# ftdi.net
KiCad netlist of a schematic drawn in Altium Designer
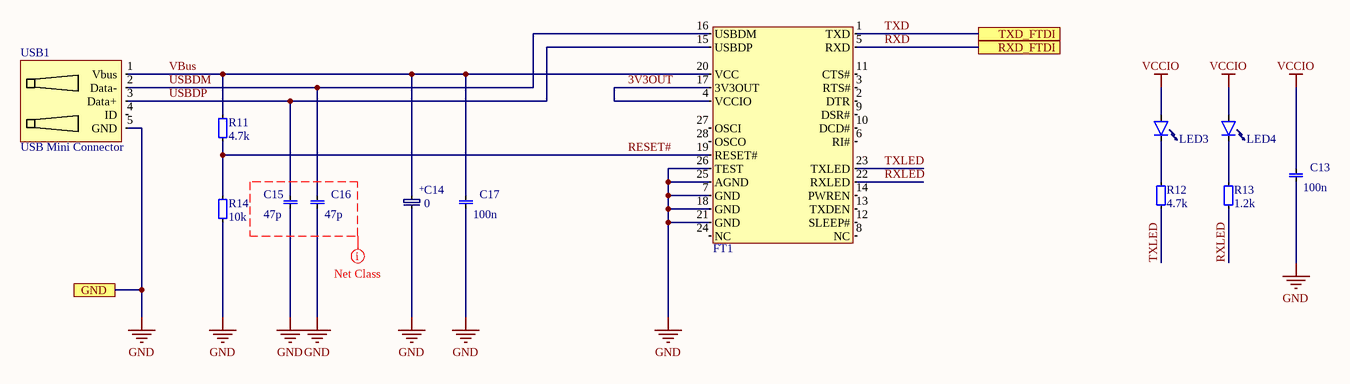
[diagram p0: ftdi.SchDoc]

(export (version "E")
  (design (tool "Eeschema 10.0.6"))
  (components
    (comp (ref "C13")
      (value "100n")
      (footprint "0603 cap")
      (fields (field (name "Comment") "0603, capacitor"))
      (libsource (lib "jclib") (part "0603, capacitor"))
    )
    (comp (ref "C14")
      (value "0")
      (footprint "CASE_B")
      (fields (field (name "Comment") "Cap, case B"))
      (libsource (lib "jclib") (part "Cap, case B"))
    )
    (comp (ref "C15")
      (value "47p")
      (footprint "0603 cap")
      (fields (field (name "Comment") "0603, capacitor"))
      (libsource (lib "jclib") (part "0603, capacitor"))
    )
    (comp (ref "C16")
      (value "47p")
      (footprint "0603 cap")
      (fields (field (name "Comment") "0603, capacitor"))
      (libsource (lib "jclib") (part "0603, capacitor"))
    )
    (comp (ref "C17")
      (value "100n")
      (footprint "0603 cap")
      (fields (field (name "Comment") "0603, capacitor"))
      (libsource (lib "jclib") (part "0603, capacitor"))
    )
    (comp (ref "FT1")
      (value "FT232R")
      (footprint "SOP28")
      (description "USB UART IC")
      (libsource (lib "jclib") (part "FT232R"))
    )
    (comp (ref "LED3")
      (value "0805, LED")
      (footprint "0805_led")
      (libsource (lib "jclib") (part "0805, LED"))
    )
    (comp (ref "LED4")
      (value "0805, LED")
      (footprint "0805_led")
      (libsource (lib "jclib") (part "0805, LED"))
    )
    (comp (ref "R11")
      (value "4.7k")
      (footprint "0603")
      (fields (field (name "Comment") "0603, resistor"))
      (libsource (lib "jclib") (part "0603, resistor"))
    )
    (comp (ref "R12")
      (value "4.7k")
      (footprint "0603")
      (fields (field (name "Comment") "0603, resistor"))
      (libsource (lib "jclib") (part "0603, resistor"))
    )
    (comp (ref "R13")
      (value "1.2k")
      (footprint "0603")
      (fields (field (name "Comment") "0603, resistor"))
      (libsource (lib "jclib") (part "0603, resistor"))
    )
    (comp (ref "R14")
      (value "10k")
      (footprint "0603")
      (fields (field (name "Comment") "0603, resistor"))
      (libsource (lib "jclib") (part "0603, resistor"))
    )
    (comp (ref "USB1")
      (value "USB Mini Connector")
      (footprint "USB Mini TH")
      (libsource (lib "jclib") (part "USB Mini Connector"))
    )
  )
  (nets
    (net (code "1") (name "/3V3OUT") (class "Default")
      (node (ref "FT1") (pin "17") (pinfunction "3V3OUT_17") (pintype "passive"))
      (node (ref "FT1") (pin "4") (pinfunction "VCCIO_4") (pintype "passive"))
    )
    (net (code "2") (name "/RESET#") (class "Default")
      (node (ref "FT1") (pin "19") (pinfunction "RESET#_19") (pintype "passive"))
      (node (ref "R11") (pin "1") (pinfunction "1_1") (pintype "passive"))
      (node (ref "R14") (pin "0") (pinfunction "0_0") (pintype "passive"))
    )
    (net (code "3") (name "/RXD") (class "Default")
      (node (ref "FT1") (pin "5") (pinfunction "RXD_5") (pintype "passive"))
    )
    (net (code "4") (name "/RXLED") (class "Default")
      (node (ref "FT1") (pin "22") (pinfunction "RXLED_22") (pintype "passive"))
      (node (ref "R13") (pin "1") (pinfunction "1_1") (pintype "passive"))
    )
    (net (code "5") (name "/TXD") (class "Default")
      (node (ref "FT1") (pin "1") (pinfunction "TXD_1") (pintype "passive"))
    )
    (net (code "6") (name "/TXLED") (class "Default")
      (node (ref "FT1") (pin "23") (pinfunction "TXLED_23") (pintype "passive"))
      (node (ref "R12") (pin "1") (pinfunction "1_1") (pintype "passive"))
    )
    (net (code "7") (name "/USBDM") (class "Default")
      (node (ref "C16") (pin "1") (pinfunction "1_1") (pintype "passive"))
      (node (ref "FT1") (pin "16") (pinfunction "USBDM_16") (pintype "passive"))
      (node (ref "USB1") (pin "2") (pinfunction "Data-_2") (pintype "passive"))
    )
    (net (code "8") (name "/USBDP") (class "Default")
      (node (ref "C15") (pin "1") (pinfunction "1_1") (pintype "passive"))
      (node (ref "FT1") (pin "15") (pinfunction "USBDP_15") (pintype "passive"))
      (node (ref "USB1") (pin "3") (pinfunction "Data+_3") (pintype "passive"))
    )
    (net (code "9") (name "/VBus") (class "Default")
      (node (ref "C14") (pin "2") (pinfunction "2_2") (pintype "passive"))
      (node (ref "C17") (pin "1") (pinfunction "1_1") (pintype "passive"))
      (node (ref "FT1") (pin "20") (pinfunction "VCC_20") (pintype "passive"))
      (node (ref "R11") (pin "0") (pinfunction "0_0") (pintype "passive"))
      (node (ref "USB1") (pin "1") (pinfunction "Vbus_1") (pintype "passive"))
    )
    (net (code "10") (name "GND") (class "Default")
      (node (ref "C13") (pin "0") (pinfunction "0_0") (pintype "passive"))
      (node (ref "C14") (pin "1") (pinfunction "1_1") (pintype "passive"))
      (node (ref "C15") (pin "0") (pinfunction "0_0") (pintype "passive"))
      (node (ref "C16") (pin "0") (pinfunction "0_0") (pintype "passive"))
      (node (ref "C17") (pin "0") (pinfunction "0_0") (pintype "passive"))
      (node (ref "FT1") (pin "18") (pinfunction "GND_18") (pintype "passive"))
      (node (ref "FT1") (pin "21") (pinfunction "GND_21") (pintype "passive"))
      (node (ref "FT1") (pin "25") (pinfunction "AGND_25") (pintype "passive"))
      (node (ref "FT1") (pin "26") (pinfunction "TEST_26") (pintype "passive"))
      (node (ref "FT1") (pin "7") (pinfunction "GND_7") (pintype "passive"))
      (node (ref "R14") (pin "1") (pinfunction "1_1") (pintype "passive"))
      (node (ref "USB1") (pin "5") (pinfunction "GND_5") (pintype "passive"))
    )
    (net (code "11") (name "Net-(LED3-Cathode)") (class "Default")
      (node (ref "LED3") (pin "0") (pinfunction "Cathode_0") (pintype "passive"))
      (node (ref "R12") (pin "0") (pinfunction "0_0") (pintype "passive"))
    )
    (net (code "12") (name "Net-(LED4-Cathode)") (class "Default")
      (node (ref "LED4") (pin "0") (pinfunction "Cathode_0") (pintype "passive"))
      (node (ref "R13") (pin "0") (pinfunction "0_0") (pintype "passive"))
    )
    (net (code "13") (name "VCCIO") (class "Default")
      (node (ref "C13") (pin "1") (pinfunction "1_1") (pintype "passive"))
      (node (ref "LED3") (pin "1") (pinfunction "1_1") (pintype "passive"))
      (node (ref "LED4") (pin "1") (pinfunction "1_1") (pintype "passive"))
    )
    (net (code "14") (name "unconnected-(FT1-CTS#-Pad11)") (class "Default")
      (node (ref "FT1") (pin "11") (pinfunction "CTS#_11") (pintype "passive"))
    )
    (net (code "15") (name "unconnected-(FT1-DCD#-Pad10)") (class "Default")
      (node (ref "FT1") (pin "10") (pinfunction "DCD#_10") (pintype "passive"))
    )
    (net (code "16") (name "unconnected-(FT1-DSR#-Pad9)") (class "Default")
      (node (ref "FT1") (pin "9") (pinfunction "DSR#_9") (pintype "passive"))
    )
    (net (code "17") (name "unconnected-(FT1-DTR-Pad2)") (class "Default")
      (node (ref "FT1") (pin "2") (pinfunction "DTR_2") (pintype "passive"))
    )
    (net (code "18") (name "unconnected-(FT1-NC-Pad8)") (class "Default")
      (node (ref "FT1") (pin "8") (pinfunction "NC_8") (pintype "passive"))
    )
    (net (code "19") (name "unconnected-(FT1-NC-Pad24)") (class "Default")
      (node (ref "FT1") (pin "24") (pinfunction "NC_24") (pintype "passive"))
    )
    (net (code "20") (name "unconnected-(FT1-OSCI-Pad27)") (class "Default")
      (node (ref "FT1") (pin "27") (pinfunction "OSCI_27") (pintype "passive"))
    )
    (net (code "21") (name "unconnected-(FT1-OSCO-Pad28)") (class "Default")
      (node (ref "FT1") (pin "28") (pinfunction "OSCO_28") (pintype "passive"))
    )
    (net (code "22") (name "unconnected-(FT1-PWREN-Pad14)") (class "Default")
      (node (ref "FT1") (pin "14") (pinfunction "PWREN_14") (pintype "passive"))
    )
    (net (code "23") (name "unconnected-(FT1-RI#-Pad6)") (class "Default")
      (node (ref "FT1") (pin "6") (pinfunction "RI#_6") (pintype "passive"))
    )
    (net (code "24") (name "unconnected-(FT1-RTS#-Pad3)") (class "Default")
      (node (ref "FT1") (pin "3") (pinfunction "RTS#_3") (pintype "passive"))
    )
    (net (code "25") (name "unconnected-(FT1-SLEEP#-Pad12)") (class "Default")
      (node (ref "FT1") (pin "12") (pinfunction "SLEEP#_12") (pintype "passive"))
    )
    (net (code "26") (name "unconnected-(FT1-TXDEN-Pad13)") (class "Default")
      (node (ref "FT1") (pin "13") (pinfunction "TXDEN_13") (pintype "passive"))
    )
    (net (code "27") (name "unconnected-(USB1-ID-Pad4)") (class "Default")
      (node (ref "USB1") (pin "4") (pinfunction "ID_4") (pintype "passive"))
    )
  )
)
